# ifamp-tx.net
KiCad netlist of a schematic drawn in Altium Designer
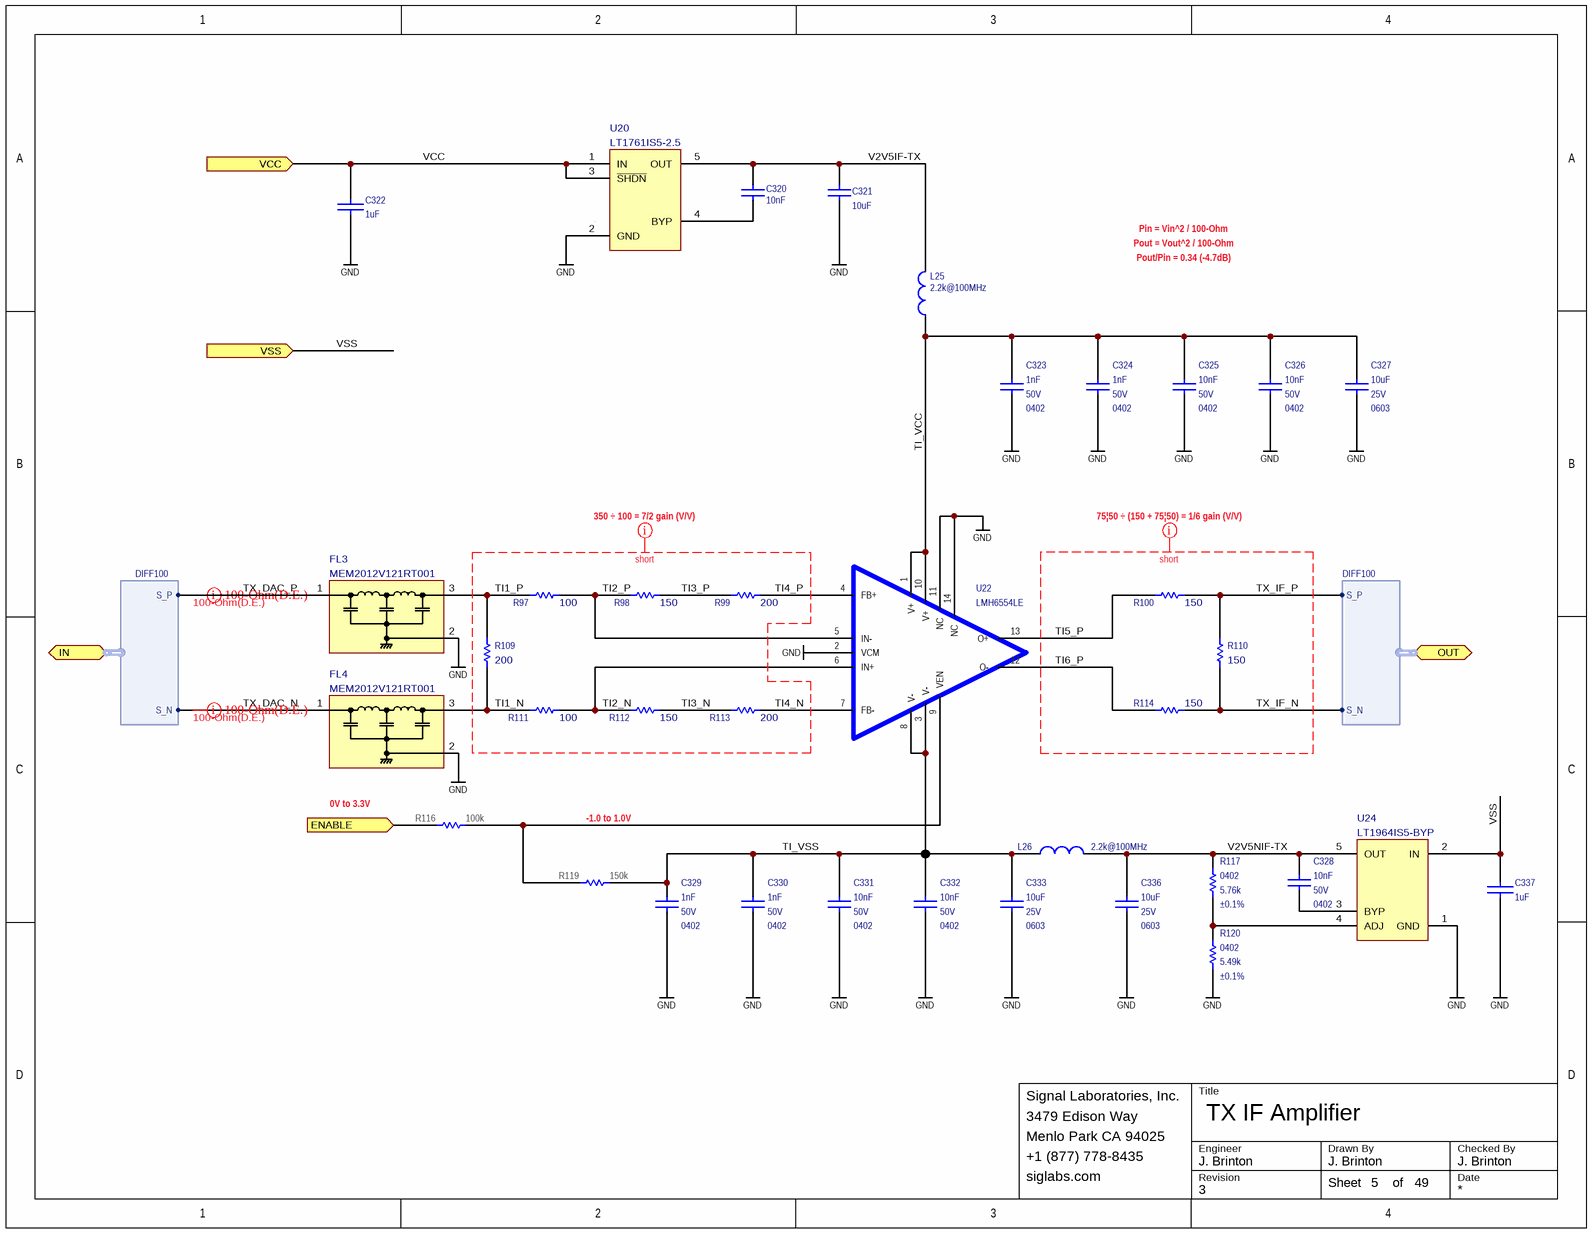
[diagram p0: ifamp-tx.SchDoc]

(export (version "E")
  (design (tool "Eeschema 10.0.6"))
  (components
    (comp (ref "C320")
      (value "10nF")
      (footprint "CAPC100X50X55L25N")
      (description "Ceramic Capacitor 10nF ±10% 50V X7R 0402")
      (fields (field (name "VOLTAGE") "50V") (field (name "MANUFACTURER") "Murata"))
      (libsource (lib "Graviton") (part "CAP 0402"))
    )
    (comp (ref "C321")
      (value "10uF")
      (footprint "CAPC160X80X90L20N")
      (description "Ceramic Capacitor 10uF ±20% 25V X5R 0603")
      (fields (field (name "MANUFACTURER") "Murata") (field (name "VOLTAGE") "25V"))
      (libsource (lib "generic") (part "CAP 0603"))
    )
    (comp (ref "C322")
      (value "1uF")
      (footprint "CAPC100X50X55L25N")
      (description "Ceramic Capacitor 1uF ±10% 10V X5R 0402")
      (fields (field (name "MANUFACTURER") "Murata") (field (name "TOLERANCE") "±10%"))
      (libsource (lib "*") (part "CAP"))
    )
    (comp (ref "C323")
      (value "1nF")
      (footprint "CAPC100X50X55L25N")
      (description "Ceramic Capacitor 1nF ±5% 50V NP0 0402")
      (fields
        (field (name "VOLTAGE") "50V")
        (field (name "MANUFACTURER") "TDK")
        (field (name "PACKAGE") "0402")
        (field (name "TOLERANCE") "±5%")
      )
      (libsource (lib "Graviton") (part "CAP 0402"))
    )
    (comp (ref "C324")
      (value "1nF")
      (footprint "CAPC100X50X55L25N")
      (description "Ceramic Capacitor 1nF ±5% 50V NP0 0402")
      (fields
        (field (name "VOLTAGE") "50V")
        (field (name "MANUFACTURER") "TDK")
        (field (name "PACKAGE") "0402")
        (field (name "TOLERANCE") "±5%")
      )
      (libsource (lib "Graviton") (part "CAP 0402"))
    )
    (comp (ref "C325")
      (value "10nF")
      (footprint "CAPC100X50X55L25N")
      (description "Ceramic Capacitor 10nF ±10% 50V X7R 0402")
      (fields
        (field (name "VOLTAGE") "50V")
        (field (name "MANUFACTURER") "Murata")
        (field (name "PACKAGE") "0402")
        (field (name "TOLERANCE") "±10%")
      )
      (libsource (lib "Graviton") (part "CAP 0402"))
    )
    (comp (ref "C326")
      (value "10nF")
      (footprint "CAPC100X50X55L25N")
      (description "Ceramic Capacitor 10nF ±10% 50V X7R 0402")
      (fields
        (field (name "VOLTAGE") "50V")
        (field (name "MANUFACTURER") "Murata")
        (field (name "PACKAGE") "0402")
        (field (name "TOLERANCE") "±10%")
      )
      (libsource (lib "Graviton") (part "CAP 0402"))
    )
    (comp (ref "C327")
      (value "10uF")
      (footprint "CAPC160X80X90L20N")
      (description "Ceramic Capacitor 10uF ±20% 25V X5R 0603")
      (fields
        (field (name "MANUFACTURER") "Murata")
        (field (name "VOLTAGE") "25V")
        (field (name "PACKAGE") "0603")
        (field (name "TOLERANCE") "±20%")
      )
      (libsource (lib "generic") (part "CAP 0603"))
    )
    (comp (ref "C328")
      (value "10nF")
      (footprint "CAPC100X50X55L25N")
      (description "Ceramic Capacitor 10nF ±10% 50V X7R 0402")
      (fields
        (field (name "VOLTAGE") "50V")
        (field (name "MANUFACTURER") "Murata")
        (field (name "PACKAGE") "0402")
        (field (name "TOLERANCE") "±10%")
      )
      (libsource (lib "Graviton") (part "CAP 0402"))
    )
    (comp (ref "C329")
      (value "1nF")
      (footprint "CAPC100X50X55L25N")
      (description "Ceramic Capacitor 1nF ±5% 50V NP0 0402")
      (fields
        (field (name "VOLTAGE") "50V")
        (field (name "MANUFACTURER") "TDK")
        (field (name "PACKAGE") "0402")
        (field (name "TOLERANCE") "±5%")
      )
      (libsource (lib "Graviton") (part "CAP 0402"))
    )
    (comp (ref "C330")
      (value "1nF")
      (footprint "CAPC100X50X55L25N")
      (description "Ceramic Capacitor 1nF ±5% 50V NP0 0402")
      (fields
        (field (name "VOLTAGE") "50V")
        (field (name "MANUFACTURER") "TDK")
        (field (name "PACKAGE") "0402")
        (field (name "TOLERANCE") "±5%")
      )
      (libsource (lib "Graviton") (part "CAP 0402"))
    )
    (comp (ref "C331")
      (value "10nF")
      (footprint "CAPC100X50X55L25N")
      (description "Ceramic Capacitor 10nF ±10% 50V X7R 0402")
      (fields
        (field (name "VOLTAGE") "50V")
        (field (name "MANUFACTURER") "Murata")
        (field (name "PACKAGE") "0402")
        (field (name "TOLERANCE") "±10%")
      )
      (libsource (lib "Graviton") (part "CAP 0402"))
    )
    (comp (ref "C332")
      (value "10nF")
      (footprint "CAPC100X50X55L25N")
      (description "Ceramic Capacitor 10nF ±10% 50V X7R 0402")
      (fields
        (field (name "VOLTAGE") "50V")
        (field (name "MANUFACTURER") "Murata")
        (field (name "PACKAGE") "0402")
        (field (name "TOLERANCE") "±10%")
      )
      (libsource (lib "Graviton") (part "CAP 0402"))
    )
    (comp (ref "C333")
      (value "10uF")
      (footprint "CAPC160X80X90L20N")
      (description "Ceramic Capacitor 10uF ±20% 25V X5R 0603")
      (fields
        (field (name "MANUFACTURER") "Murata")
        (field (name "VOLTAGE") "25V")
        (field (name "PACKAGE") "0603")
        (field (name "TOLERANCE") "±20%")
      )
      (libsource (lib "generic") (part "CAP 0603"))
    )
    (comp (ref "C336")
      (value "10uF")
      (footprint "CAPC160X80X90L20N")
      (description "Ceramic Capacitor 10uF ±20% 25V X5R 0603")
      (fields
        (field (name "MANUFACTURER") "Murata")
        (field (name "VOLTAGE") "25V")
        (field (name "PACKAGE") "0603")
        (field (name "TOLERANCE") "±20%")
      )
      (libsource (lib "generic") (part "CAP 0603"))
    )
    (comp (ref "C337")
      (value "1uF")
      (footprint "CAPC100X50X55L25N")
      (description "Ceramic Capacitor 1uF ±10% 10V X5R 0402")
      (fields (field (name "MANUFACTURER") "Murata") (field (name "TOLERANCE") "±10%"))
      (libsource (lib "*") (part "CAP"))
    )
    (comp (ref "FL3")
      (value "MEM2012V121RT001")
      (footprint "tdk:MEM2012V")
      (description "MEM2012 Series 120 MHz 10V 100mA SMT Signal Line 3-Terminal Filter")
      (fields (field (name "MANUFACTURER") "TDK"))
      (libsource (lib "tdk") (part "MEM2012V121RT001"))
    )
    (comp (ref "FL4")
      (value "MEM2012V121RT001")
      (footprint "tdk:MEM2012V")
      (description "MEM2012 Series 120 MHz 10V 100mA SMT Signal Line 3-Terminal Filter")
      (fields (field (name "MANUFACTURER") "TDK"))
      (libsource (lib "tdk") (part "MEM2012V121RT001"))
    )
    (comp (ref "L25")
      (value "2.2k@100MHz")
      (footprint "INDC1005X55N")
      (description "Ferrite Bead 2.2k@100MHz 150mA 0402")
      (fields (field (name "MANUFACTURER") "TDK") (field (name "Comment") "MMZ1005A222ET000"))
      (libsource (lib "*") (part "INDUCTANCE1"))
    )
    (comp (ref "L26")
      (value "2.2k@100MHz")
      (footprint "INDC1005X55N")
      (description "Ferrite Bead 2.2k@100MHz 150mA 0402")
      (fields (field (name "MANUFACTURER") "TDK") (field (name "Comment") "MMZ1005A222ET000"))
      (libsource (lib "*") (part "INDUCTANCE1"))
    )
    (comp (ref "R97")
      (value "100")
      (footprint "generic:RESC1608X55N")
      (description "Thin Film Resistor 100 Ohm ±0.5% 0603")
      (fields (field (name "MANUFACTURER") "Vishay") (field (name "TOLERANCE") "±0.5%"))
      (libsource (lib "Graviton") (part "RES 0603"))
    )
    (comp (ref "R98")
      (value "150")
      (footprint "generic:RESC1608X55N")
      (description "Thin Film Resistor 150 Ohm ±0.5% 0603")
      (fields (field (name "MANUFACTURER") "Vishay") (field (name "TOLERANCE") "±0.5%"))
      (libsource (lib "Graviton") (part "RES 0603"))
    )
    (comp (ref "R99")
      (value "200")
      (footprint "generic:RESC1608X55N")
      (description "Thin Film Resistor 200 Ohm ±1% 0603")
      (fields (field (name "MANUFACTURER") "Vishay") (field (name "TOLERANCE") "±1%"))
      (libsource (lib "Graviton") (part "RES 0603"))
    )
    (comp (ref "R100")
      (value "150")
      (footprint "generic:RESC1608X55N")
      (description "Thin Film Resistor 150 Ohm ±0.5% 0603")
      (fields (field (name "MANUFACTURER") "Vishay") (field (name "TOLERANCE") "±0.5%"))
      (libsource (lib "Graviton") (part "RES 0603"))
    )
    (comp (ref "R109")
      (value "200")
      (footprint "generic:RESC1608X55N")
      (description "Thin Film Resistor 200 Ohm ±1% 0603")
      (fields (field (name "MANUFACTURER") "Vishay") (field (name "TOLERANCE") "±1%"))
      (libsource (lib "Graviton") (part "RES 0603"))
    )
    (comp (ref "R110")
      (value "150")
      (footprint "generic:RESC1608X55N")
      (description "Thin Film Resistor 150 Ohm ±0.5% 0603")
      (fields (field (name "MANUFACTURER") "Vishay") (field (name "TOLERANCE") "±0.5%"))
      (libsource (lib "Graviton") (part "RES 0603"))
    )
    (comp (ref "R111")
      (value "100")
      (footprint "generic:RESC1608X55N")
      (description "Thin Film Resistor 100 Ohm ±0.5% 0603")
      (fields (field (name "MANUFACTURER") "Vishay") (field (name "TOLERANCE") "±0.5%"))
      (libsource (lib "Graviton") (part "RES 0603"))
    )
    (comp (ref "R112")
      (value "150")
      (footprint "generic:RESC1608X55N")
      (description "Thin Film Resistor 150 Ohm ±0.5% 0603")
      (fields (field (name "MANUFACTURER") "Vishay") (field (name "TOLERANCE") "±0.5%"))
      (libsource (lib "Graviton") (part "RES 0603"))
    )
    (comp (ref "R113")
      (value "200")
      (footprint "generic:RESC1608X55N")
      (description "Thin Film Resistor 200 Ohm ±1% 0603")
      (fields (field (name "MANUFACTURER") "Vishay") (field (name "TOLERANCE") "±1%"))
      (libsource (lib "Graviton") (part "RES 0603"))
    )
    (comp (ref "R114")
      (value "150")
      (footprint "generic:RESC1608X55N")
      (description "Thin Film Resistor 150 Ohm ±0.5% 0603")
      (fields (field (name "MANUFACTURER") "Vishay") (field (name "TOLERANCE") "±0.5%"))
      (libsource (lib "Graviton") (part "RES 0603"))
    )
    (comp (ref "R116")
      (value "100k")
      (footprint "RESC1005X40N")
      (description "Thick Film Resistor 100k ±1% 0.1W 50V 0402")
      (fields (field (name "MANUFACTURER") "Panasonic") (field (name "TOLERANCE") "±1%"))
      (libsource (lib "generic") (part "RES"))
    )
    (comp (ref "R117")
      (value "5.76k")
      (footprint "RESC1005X40N")
      (description "Thin Film Resistor 5.76k +/-0.1% SMD 0402")
      (fields
        (field (name "TOLERANCE") "±0.1%")
        (field (name "MANUFACTURER") "Yageo")
        (field (name "PACKAGE") "0402")
        (field (name "Comment") "RT0402BRE075K76L")
      )
      (libsource (lib "generic") (part "RES"))
    )
    (comp (ref "R119")
      (value "150k")
      (footprint "RESC1005X40N")
      (description "Thick Film Resistor 150k ±1% 0.1W 50V 0402")
      (fields (field (name "MANUFACTURER") "Panasonic") (field (name "TOLERANCE") "±1%"))
      (libsource (lib "generic") (part "RES"))
    )
    (comp (ref "R120")
      (value "5.49k")
      (footprint "RESC1005X40N")
      (description "Thin Film Resistor 5.49k +/-0.1% SMD 0402")
      (fields
        (field (name "TOLERANCE") "±0.1%")
        (field (name "MANUFACTURER") "Panasonic")
        (field (name "PACKAGE") "0402")
        (field (name "Comment") "ERA-2AEB5491X")
      )
      (libsource (lib "generic") (part "RES"))
    )
    (comp (ref "U20")
      (value "LT1761IS5-2.5")
      (footprint "TSOT-5")
      (description "100mA Low Noise LDO 5V")
      (fields (field (name "MANUFACTURER") "Linear Technology"))
      (libsource (lib "linear") (part "LT1761IS5-5"))
    )
    (comp (ref "U22")
      (value "LMH6554LE")
      (footprint "texas_instruments:NHJ0014A")
      (description "2.8 GHz Ultra Linear Fully Differential Amplifier")
      (fields (field (name "MANUFACTURER") "Texas Instruments"))
      (libsource (lib "ti") (part "LMH6554LE"))
    )
    (comp (ref "U24")
      (value "LT1964IS5-BYP")
      (footprint "SOT23-5")
      (description "200mA Low Noise negative-LDO")
      (fields (field (name "MANUFACTURER") "Linear Technology"))
      (libsource (lib "linear") (part "LT1964IS5-BYP"))
    )
  )
  (nets
    (net (code "2") (name "/ENABLE") (class "Default")
      (node (ref "R116") (pin "2") (pinfunction "2_2") (pintype "passive"))
    )
    (net (code "3") (name "/TI1_N") (class "Default")
      (node (ref "FL4") (pin "3") (pinfunction "OUT/IN_3") (pintype "passive"))
      (node (ref "R109") (pin "1") (pinfunction "1_1") (pintype "passive"))
      (node (ref "R111") (pin "1") (pinfunction "1_1") (pintype "passive"))
    )
    (net (code "4") (name "/TI1_P") (class "Default")
      (node (ref "FL3") (pin "3") (pinfunction "OUT/IN_3") (pintype "passive"))
      (node (ref "R109") (pin "2") (pinfunction "2_2") (pintype "passive"))
      (node (ref "R97") (pin "1") (pinfunction "1_1") (pintype "passive"))
    )
    (net (code "5") (name "/TI2_N") (class "Default")
      (node (ref "R111") (pin "2") (pinfunction "2_2") (pintype "passive"))
      (node (ref "R112") (pin "1") (pinfunction "1_1") (pintype "passive"))
      (node (ref "U22") (pin "6") (pinfunction "IN+_6") (pintype "passive"))
    )
    (net (code "6") (name "/TI2_P") (class "Default")
      (node (ref "R97") (pin "2") (pinfunction "2_2") (pintype "passive"))
      (node (ref "R98") (pin "1") (pinfunction "1_1") (pintype "passive"))
      (node (ref "U22") (pin "5") (pinfunction "IN-_5") (pintype "passive"))
    )
    (net (code "7") (name "/TI3_N") (class "Default")
      (node (ref "R112") (pin "2") (pinfunction "2_2") (pintype "passive"))
      (node (ref "R113") (pin "1") (pinfunction "1_1") (pintype "passive"))
    )
    (net (code "8") (name "/TI3_P") (class "Default")
      (node (ref "R98") (pin "2") (pinfunction "2_2") (pintype "passive"))
      (node (ref "R99") (pin "1") (pinfunction "1_1") (pintype "passive"))
    )
    (net (code "9") (name "/TI4_N") (class "Default")
      (node (ref "R113") (pin "2") (pinfunction "2_2") (pintype "passive"))
      (node (ref "U22") (pin "7") (pinfunction "FB-_7") (pintype "passive"))
    )
    (net (code "10") (name "/TI4_P") (class "Default")
      (node (ref "R99") (pin "2") (pinfunction "2_2") (pintype "passive"))
      (node (ref "U22") (pin "4") (pinfunction "FB+_4") (pintype "passive"))
    )
    (net (code "11") (name "/TI5_P") (class "Default")
      (node (ref "R100") (pin "1") (pinfunction "1_1") (pintype "passive"))
      (node (ref "U22") (pin "13") (pinfunction "O+_13") (pintype "passive"))
    )
    (net (code "12") (name "/TI6_P") (class "Default")
      (node (ref "R114") (pin "1") (pinfunction "1_1") (pintype "passive"))
      (node (ref "U22") (pin "12") (pinfunction "O-_12") (pintype "passive"))
    )
    (net (code "13") (name "/TI_VCC") (class "Default")
      (node (ref "C323") (pin "2") (pinfunction "2_2") (pintype "passive"))
      (node (ref "C324") (pin "2") (pinfunction "2_2") (pintype "passive"))
      (node (ref "C325") (pin "2") (pinfunction "2_2") (pintype "passive"))
      (node (ref "C326") (pin "2") (pinfunction "2_2") (pintype "passive"))
      (node (ref "C327") (pin "2") (pinfunction "2_2") (pintype "passive"))
      (node (ref "L25") (pin "1") (pinfunction "1_1") (pintype "passive"))
      (node (ref "U22") (pin "1") (pinfunction "V+_1") (pintype "passive"))
      (node (ref "U22") (pin "10") (pinfunction "V+_10") (pintype "passive"))
    )
    (net (code "14") (name "/TI_VSS") (class "Default")
      (node (ref "C329") (pin "2") (pinfunction "2_2") (pintype "passive"))
      (node (ref "C330") (pin "2") (pinfunction "2_2") (pintype "passive"))
      (node (ref "C331") (pin "2") (pinfunction "2_2") (pintype "passive"))
      (node (ref "C332") (pin "2") (pinfunction "2_2") (pintype "passive"))
      (node (ref "C333") (pin "2") (pinfunction "2_2") (pintype "passive"))
      (node (ref "L26") (pin "1") (pinfunction "1_1") (pintype "passive"))
      (node (ref "R119") (pin "1") (pinfunction "1_1") (pintype "passive"))
      (node (ref "U22") (pin "3") (pinfunction "V-_3") (pintype "passive"))
      (node (ref "U22") (pin "8") (pinfunction "V-_8") (pintype "passive"))
    )
    (net (code "15") (name "/TX_DAC_N") (class "Default")
      (node (ref "FL4") (pin "1") (pinfunction "IN/OUT_1") (pintype "passive"))
    )
    (net (code "16") (name "/TX_DAC_P") (class "Default")
      (node (ref "FL3") (pin "1") (pinfunction "IN/OUT_1") (pintype "passive"))
    )
    (net (code "17") (name "/TX_IF_N") (class "Default")
      (node (ref "R110") (pin "1") (pinfunction "1_1") (pintype "passive"))
      (node (ref "R114") (pin "2") (pinfunction "2_2") (pintype "passive"))
    )
    (net (code "18") (name "/TX_IF_P") (class "Default")
      (node (ref "R100") (pin "2") (pinfunction "2_2") (pintype "passive"))
      (node (ref "R110") (pin "2") (pinfunction "2_2") (pintype "passive"))
    )
    (net (code "19") (name "/V2V5IF-TX") (class "Default")
      (node (ref "C320") (pin "2") (pinfunction "2_2") (pintype "passive"))
      (node (ref "C321") (pin "2") (pinfunction "2_2") (pintype "passive"))
      (node (ref "L25") (pin "2") (pinfunction "2_2") (pintype "passive"))
      (node (ref "U20") (pin "5") (pinfunction "OUT_5") (pintype "passive"))
    )
    (net (code "20") (name "/V2V5NIF-TX") (class "Default")
      (node (ref "C328") (pin "2") (pinfunction "2_2") (pintype "passive"))
      (node (ref "C336") (pin "2") (pinfunction "2_2") (pintype "passive"))
      (node (ref "L26") (pin "2") (pinfunction "2_2") (pintype "passive"))
      (node (ref "R117") (pin "2") (pinfunction "2_2") (pintype "passive"))
      (node (ref "U24") (pin "5") (pinfunction "OUT_5") (pintype "passive"))
    )
    (net (code "21") (name "/VCC") (class "Default")
      (node (ref "C322") (pin "2") (pinfunction "2_2") (pintype "passive"))
      (node (ref "U20") (pin "1") (pinfunction "IN_1") (pintype "passive"))
      (node (ref "U20") (pin "3") (pinfunction "SHDN_3") (pintype "passive"))
    )
    (net (code "22") (name "/VSS") (class "Default")
      (node (ref "C337") (pin "2") (pinfunction "2_2") (pintype "passive"))
      (node (ref "U24") (pin "2") (pinfunction "IN_2") (pintype "passive"))
    )
    (net (code "24") (name "GND") (class "Default")
      (node (ref "C321") (pin "1") (pinfunction "1_1") (pintype "passive"))
      (node (ref "C322") (pin "1") (pinfunction "1_1") (pintype "passive"))
      (node (ref "C323") (pin "1") (pinfunction "1_1") (pintype "passive"))
      (node (ref "C324") (pin "1") (pinfunction "1_1") (pintype "passive"))
      (node (ref "C325") (pin "1") (pinfunction "1_1") (pintype "passive"))
      (node (ref "C326") (pin "1") (pinfunction "1_1") (pintype "passive"))
      (node (ref "C327") (pin "1") (pinfunction "1_1") (pintype "passive"))
      (node (ref "C329") (pin "1") (pinfunction "1_1") (pintype "passive"))
      (node (ref "C330") (pin "1") (pinfunction "1_1") (pintype "passive"))
      (node (ref "C331") (pin "1") (pinfunction "1_1") (pintype "passive"))
      (node (ref "C332") (pin "1") (pinfunction "1_1") (pintype "passive"))
      (node (ref "C333") (pin "1") (pinfunction "1_1") (pintype "passive"))
      (node (ref "C336") (pin "1") (pinfunction "1_1") (pintype "passive"))
      (node (ref "C337") (pin "1") (pinfunction "1_1") (pintype "passive"))
      (node (ref "FL3") (pin "2") (pinfunction "GND_2") (pintype "power_in"))
      (node (ref "FL4") (pin "2") (pinfunction "GND_2") (pintype "power_in"))
      (node (ref "R120") (pin "1") (pinfunction "1_1") (pintype "passive"))
      (node (ref "U20") (pin "2") (pinfunction "GND_2") (pintype "passive"))
      (node (ref "U22") (pin "11") (pinfunction "NC_11") (pintype "passive"))
      (node (ref "U22") (pin "14") (pinfunction "NC_14") (pintype "passive"))
      (node (ref "U22") (pin "2") (pinfunction "VCM_2") (pintype "passive"))
      (node (ref "U24") (pin "1") (pinfunction "GND_1") (pintype "passive"))
    )
    (net (code "25") (name "Net-(U20-BYP)") (class "Default")
      (node (ref "C320") (pin "1") (pinfunction "1_1") (pintype "passive"))
      (node (ref "U20") (pin "4") (pinfunction "BYP_4") (pintype "passive"))
    )
    (net (code "26") (name "Net-(U22-VEN)") (class "Default")
      (node (ref "R116") (pin "1") (pinfunction "1_1") (pintype "passive"))
      (node (ref "R119") (pin "2") (pinfunction "2_2") (pintype "passive"))
      (node (ref "U22") (pin "9") (pinfunction "VEN_9") (pintype "passive"))
    )
    (net (code "27") (name "Net-(U24-ADJ)") (class "Default")
      (node (ref "R117") (pin "1") (pinfunction "1_1") (pintype "passive"))
      (node (ref "R120") (pin "2") (pinfunction "2_2") (pintype "passive"))
      (node (ref "U24") (pin "4") (pinfunction "ADJ_4") (pintype "passive"))
    )
    (net (code "28") (name "Net-(U24-BYP)") (class "Default")
      (node (ref "C328") (pin "1") (pinfunction "1_1") (pintype "passive"))
      (node (ref "U24") (pin "3") (pinfunction "BYP_3") (pintype "passive"))
    )
  )
)
